# salinity.net
KiCad netlist of a schematic drawn in Altium Designer
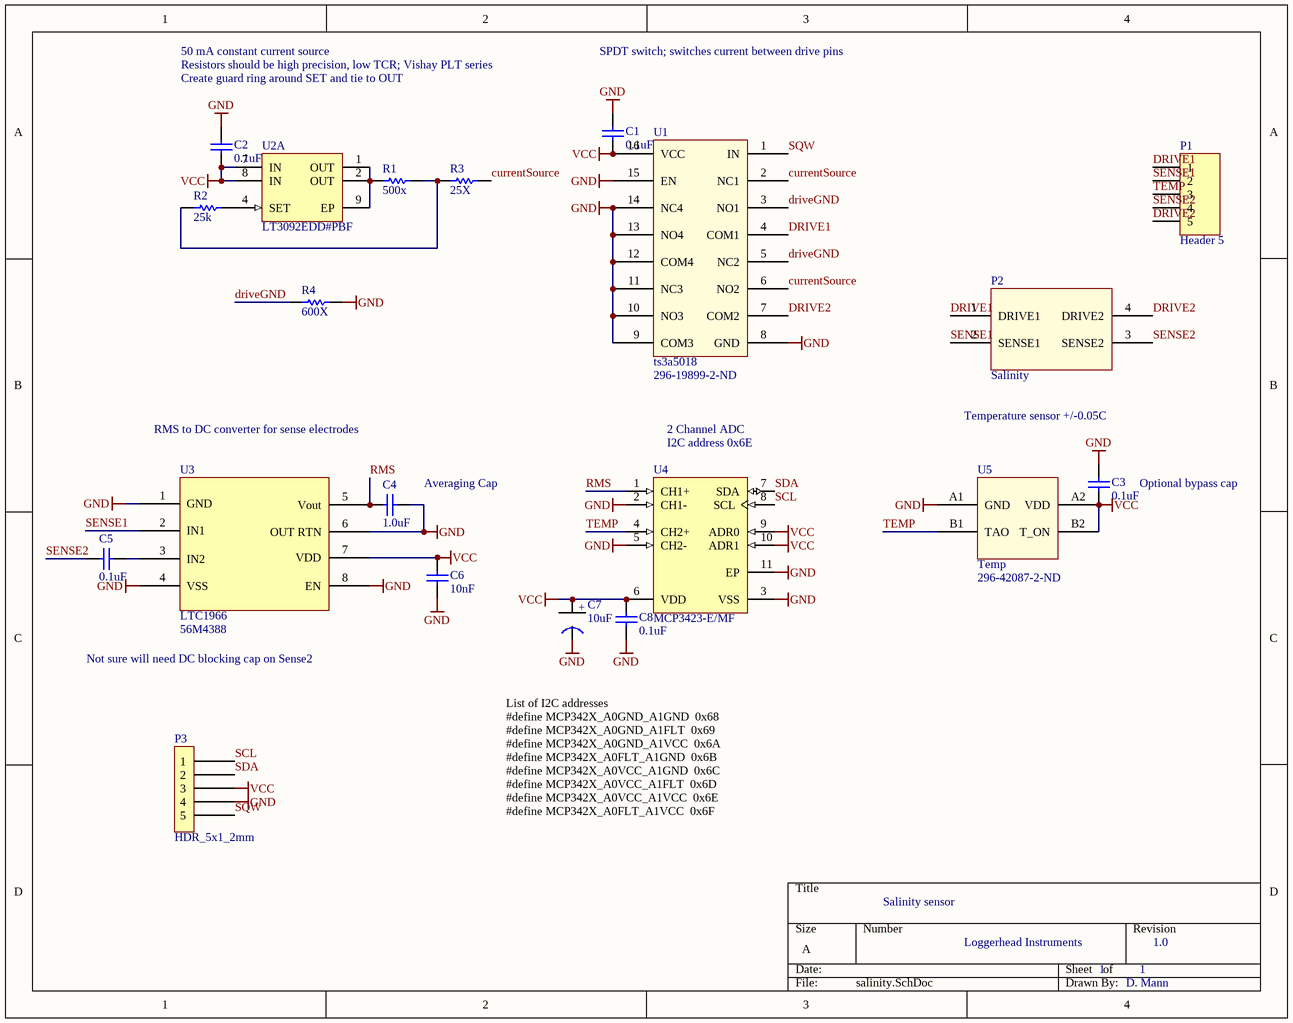
[diagram p0: salinity.SchDoc]

(export (version "E")
  (design (tool "Eeschema 10.0.6"))
  (components
    (comp (ref "C1")
      (value "0.1uF")
      (footprint "0402")
      (description "Ceramic Chip Capacitor - Standard")
      (fields (field (name "PUBLISHER") "Altium Limited"))
      (libsource (lib "KEMET Chip Capacitor") (part "C0402"))
    )
    (comp (ref "C2")
      (value "0.1uF")
      (footprint "0402")
      (description "Ceramic Chip Capacitor - Standard")
      (fields (field (name "PUBLISHER") "Altium Limited"))
      (libsource (lib "KEMET Chip Capacitor") (part "C0402"))
    )
    (comp (ref "C3")
      (value "0.1uF")
      (footprint "0402")
      (description "Ceramic Chip Capacitor - Standard")
      (fields (field (name "PUBLISHER") "Altium Limited"))
      (libsource (lib "KEMET Chip Capacitor") (part "C0402"))
    )
    (comp (ref "C4")
      (value "1.0uF")
      (footprint "0402")
      (description "Ceramic Chip Capacitor - Standard")
      (fields (field (name "PUBLISHER") "Altium Limited"))
      (libsource (lib "KEMET Chip Capacitor") (part "C0402"))
    )
    (comp (ref "C5")
      (value "0.1uF")
      (footprint "0402")
      (description "Ceramic Chip Capacitor - Standard")
      (fields (field (name "PUBLISHER") "Altium Limited"))
      (libsource (lib "KEMET Chip Capacitor") (part "C0402"))
    )
    (comp (ref "C6")
      (value "10nF")
      (footprint "0402")
      (description "Ceramic Chip Capacitor - Standard")
      (fields (field (name "PUBLISHER") "Altium Limited"))
      (libsource (lib "KEMET Chip Capacitor") (part "C0402"))
    )
    (comp (ref "C7") (value "10uF") (footprint "Tant0805") (libsource (lib "Loggerhead") (part "Tant0805")))
    (comp (ref "C8")
      (value "0.1uF")
      (footprint "0402")
      (description "Ceramic Chip Capacitor - Standard")
      (fields (field (name "PUBLISHER") "Altium Limited"))
      (libsource (lib "KEMET Chip Capacitor") (part "C0402"))
    )
    (comp (ref "P1")
      (value "Header 5")
      (footprint "HDR1X5")
      (description "Header, 5-Pin")
      (fields (field (name "PUBLISHER") "Altium Limited"))
      (libsource (lib "Miscellaneous Connectors") (part "Header 5"))
    )
    (comp (ref "P2")
      (value "Salinity")
      (footprint "SALINITY")
      (libsource (lib "Loggerhead") (part "SALINITY"))
    )
    (comp (ref "P3")
      (value "HDR_5x1_2mm")
      (footprint "Hdr_5x1_2mm")
      (libsource (lib "Loggerhead") (part "HDR_5x1_2mm"))
    )
    (comp (ref "R1")
      (value "500x")
      (footprint "3-0603")
      (fields (field (name "PUBLISHER") "Altium Limited"))
      (libsource (lib "Panasonic Resistor") (part "ERJ3BQ"))
    )
    (comp (ref "R2")
      (value "25k")
      (footprint "3-0603")
      (fields (field (name "PUBLISHER") "Altium Limited"))
      (libsource (lib "Panasonic Resistor") (part "ERJ3BQ"))
    )
    (comp (ref "R3")
      (value "25X")
      (footprint "3-0603")
      (fields (field (name "PUBLISHER") "Altium Limited"))
      (libsource (lib "Panasonic Resistor") (part "ERJ3BQ"))
    )
    (comp (ref "R4")
      (value "600X")
      (footprint "3-0603")
      (fields (field (name "PUBLISHER") "Altium Limited"))
      (libsource (lib "Panasonic Resistor") (part "ERJ3BQ"))
    )
    (comp (ref "U1")
      (value "ts3a5018")
      (footprint "ts3a5018_VQFN")
      (description "Quad SPDT")
      (fields (field (name "SUPPLIER PART NUMBER 1") "296-19899-2-ND"))
      (libsource (lib "Loggerhead") (part "ts3a5018"))
    )
    (comp (ref "U2")
      (value "LT3092EDD#PBF")
      (footprint "LT-DD-8_V")
      (fields (field (name "MANUFACTURER") "Linear Technology"))
      (libsource (lib "Linear Technology Power Management Current Sources") (part "LT3092EDD#PBF"))
    )
    (comp (ref "U3")
      (value "LTC1966")
      (footprint "MSOP8-LTC1966")
      (fields (field (name "SUPPLIER PART NUMBER 1") "56M4388"))
      (libsource (lib "Loggerhead") (part "LTC1966"))
    )
    (comp (ref "U4")
      (value "MCP3423-E/MF")
      (footprint "DFN-MF10")
      (fields (field (name "MANUFACTURER") "Microchip"))
      (libsource (lib "Microchip Mixed Signal") (part "MCP3423-E/MF"))
    )
    (comp (ref "U5")
      (value "Temp")
      (footprint "BGA4_TMP103")
      (fields (field (name "SUPPLIER PART NUMBER 1") "296-42087-2-ND"))
      (libsource (lib "Loggerhead") (part "LMT70"))
    )
  )
  (nets
    (net (code "1") (name "/DRIVE1") (class "Default")
      (node (ref "P1") (pin "1") (pinfunction "1_1") (pintype "passive"))
      (node (ref "P2") (pin "1") (pinfunction "DRIVE1_1") (pintype "passive"))
      (node (ref "U1") (pin "4") (pinfunction "COM1_4") (pintype "passive"))
    )
    (net (code "2") (name "/DRIVE2") (class "Default")
      (node (ref "P1") (pin "5") (pinfunction "5_5") (pintype "passive"))
      (node (ref "P2") (pin "4") (pinfunction "DRIVE2_4") (pintype "passive"))
      (node (ref "U1") (pin "7") (pinfunction "COM2_7") (pintype "passive"))
    )
    (net (code "3") (name "/RMS") (class "Default")
      (node (ref "C4") (pin "1") (pinfunction "1_1") (pintype "passive"))
      (node (ref "U3") (pin "5") (pinfunction "Vout_5") (pintype "passive"))
      (node (ref "U4") (pin "1") (pinfunction "CH1+_1") (pintype "input"))
    )
    (net (code "4") (name "/SCL") (class "Default")
      (node (ref "P3") (pin "1") (pinfunction "1_1") (pintype "passive"))
      (node (ref "U4") (pin "8") (pinfunction "SCL_8") (pintype "input"))
    )
    (net (code "5") (name "/SDA") (class "Default")
      (node (ref "P3") (pin "2") (pinfunction "2_2") (pintype "passive"))
      (node (ref "U4") (pin "7") (pinfunction "SDA_7") (pintype "bidirectional"))
    )
    (net (code "6") (name "/SENSE1") (class "Default")
      (node (ref "P1") (pin "2") (pinfunction "2_2") (pintype "passive"))
      (node (ref "P2") (pin "2") (pinfunction "SENSE1_2") (pintype "passive"))
      (node (ref "U3") (pin "2") (pinfunction "IN1_2") (pintype "passive"))
    )
    (net (code "7") (name "/SENSE2") (class "Default")
      (node (ref "C5") (pin "1") (pinfunction "1_1") (pintype "passive"))
      (node (ref "P1") (pin "4") (pinfunction "4_4") (pintype "passive"))
      (node (ref "P2") (pin "3") (pinfunction "SENSE2_3") (pintype "passive"))
    )
    (net (code "8") (name "/SQW") (class "Default")
      (node (ref "P3") (pin "5") (pinfunction "5_5") (pintype "passive"))
      (node (ref "U1") (pin "1") (pinfunction "IN_1") (pintype "passive"))
    )
    (net (code "9") (name "/TEMP") (class "Default")
      (node (ref "P1") (pin "3") (pinfunction "3_3") (pintype "passive"))
      (node (ref "U4") (pin "4") (pinfunction "CH2+_4") (pintype "input"))
      (node (ref "U5") (pin "B1") (pinfunction "TAO_B1") (pintype "passive"))
    )
    (net (code "10") (name "/currentSource") (class "Default")
      (node (ref "R3") (pin "2") (pinfunction "2_2") (pintype "passive"))
      (node (ref "U1") (pin "2") (pinfunction "NC1_2") (pintype "passive"))
      (node (ref "U1") (pin "6") (pinfunction "NO2_6") (pintype "passive"))
    )
    (net (code "11") (name "/driveGND") (class "Default")
      (node (ref "R4") (pin "1") (pinfunction "1_1") (pintype "passive"))
      (node (ref "U1") (pin "3") (pinfunction "NO1_3") (pintype "passive"))
      (node (ref "U1") (pin "5") (pinfunction "NC2_5") (pintype "passive"))
    )
    (net (code "12") (name "GND") (class "Default")
      (node (ref "C1") (pin "1") (pinfunction "1_1") (pintype "passive"))
      (node (ref "C2") (pin "1") (pinfunction "1_1") (pintype "passive"))
      (node (ref "C3") (pin "1") (pinfunction "1_1") (pintype "passive"))
      (node (ref "C4") (pin "2") (pinfunction "2_2") (pintype "passive"))
      (node (ref "C6") (pin "1") (pinfunction "1_1") (pintype "passive"))
      (node (ref "C7") (pin "1") (pinfunction "GND_1") (pintype "passive"))
      (node (ref "C8") (pin "1") (pinfunction "1_1") (pintype "passive"))
      (node (ref "P3") (pin "4") (pinfunction "4_4") (pintype "passive"))
      (node (ref "R4") (pin "2") (pinfunction "2_2") (pintype "passive"))
      (node (ref "U1") (pin "10") (pinfunction "NO3_10") (pintype "passive"))
      (node (ref "U1") (pin "11") (pinfunction "NC3_11") (pintype "passive"))
      (node (ref "U1") (pin "12") (pinfunction "COM4_12") (pintype "passive"))
      (node (ref "U1") (pin "13") (pinfunction "NO4_13") (pintype "passive"))
      (node (ref "U1") (pin "14") (pinfunction "NC4_14") (pintype "passive"))
      (node (ref "U1") (pin "15") (pinfunction "EN_15") (pintype "passive"))
      (node (ref "U1") (pin "8") (pinfunction "GND_8") (pintype "passive"))
      (node (ref "U1") (pin "9") (pinfunction "COM3_9") (pintype "passive"))
      (node (ref "U3") (pin "1") (pinfunction "GND_1") (pintype "passive"))
      (node (ref "U3") (pin "4") (pinfunction "VSS_4") (pintype "passive"))
      (node (ref "U3") (pin "6") (pinfunction "OUT_RTN_6") (pintype "passive"))
      (node (ref "U3") (pin "8") (pinfunction "EN_8") (pintype "passive"))
      (node (ref "U4") (pin "11") (pinfunction "EP_11") (pintype "passive"))
      (node (ref "U4") (pin "2") (pinfunction "CH1-_2") (pintype "input"))
      (node (ref "U4") (pin "3") (pinfunction "VSS_3") (pintype "power_in"))
      (node (ref "U4") (pin "5") (pinfunction "CH2-_5") (pintype "input"))
      (node (ref "U5") (pin "A1") (pinfunction "GND_A1") (pintype "passive"))
    )
    (net (code "13") (name "Net-(R1-Pad2)") (class "Default")
      (node (ref "R1") (pin "2") (pinfunction "2_2") (pintype "passive"))
      (node (ref "R2") (pin "1") (pinfunction "1_1") (pintype "passive"))
      (node (ref "R3") (pin "1") (pinfunction "1_1") (pintype "passive"))
    )
    (net (code "14") (name "Net-(U2A-EP)") (class "Default")
      (node (ref "R1") (pin "1") (pinfunction "1_1") (pintype "passive"))
      (node (ref "U2") (pin "1") (pinfunction "OUT_1") (pintype "power_in"))
      (node (ref "U2") (pin "2") (pinfunction "OUT_2") (pintype "power_in"))
      (node (ref "U2") (pin "9") (pinfunction "EP_9") (pintype "power_in"))
    )
    (net (code "15") (name "Net-(U2A-SET)") (class "Default")
      (node (ref "R2") (pin "2") (pinfunction "2_2") (pintype "passive"))
      (node (ref "U2") (pin "4") (pinfunction "SET_4") (pintype "input"))
    )
    (net (code "16") (name "Net-(U3-IN2)") (class "Default")
      (node (ref "C5") (pin "2") (pinfunction "2_2") (pintype "passive"))
      (node (ref "U3") (pin "3") (pinfunction "IN2_3") (pintype "passive"))
    )
    (net (code "17") (name "VCC") (class "Default")
      (node (ref "C1") (pin "2") (pinfunction "2_2") (pintype "passive"))
      (node (ref "C2") (pin "2") (pinfunction "2_2") (pintype "passive"))
      (node (ref "C3") (pin "2") (pinfunction "2_2") (pintype "passive"))
      (node (ref "C6") (pin "2") (pinfunction "2_2") (pintype "passive"))
      (node (ref "C7") (pin "2") (pinfunction "+_2") (pintype "passive"))
      (node (ref "C8") (pin "2") (pinfunction "2_2") (pintype "passive"))
      (node (ref "P3") (pin "3") (pinfunction "3_3") (pintype "passive"))
      (node (ref "U1") (pin "16") (pinfunction "VCC_16") (pintype "passive"))
      (node (ref "U2") (pin "7") (pinfunction "IN_7") (pintype "power_in"))
      (node (ref "U2") (pin "8") (pinfunction "IN_8") (pintype "power_in"))
      (node (ref "U3") (pin "7") (pinfunction "VDD_7") (pintype "power_in"))
      (node (ref "U4") (pin "10") (pinfunction "ADR1_10") (pintype "input"))
      (node (ref "U4") (pin "6") (pinfunction "VDD_6") (pintype "power_in"))
      (node (ref "U4") (pin "9") (pinfunction "ADR0_9") (pintype "input"))
      (node (ref "U5") (pin "A2") (pinfunction "VDD_A2") (pintype "passive"))
      (node (ref "U5") (pin "B2") (pinfunction "T_ON_B2") (pintype "passive"))
    )
  )
)
